# SparkFun_Color_Sensor_OPT4048.net
KiCad netlist of a schematic drawn in EAGLE
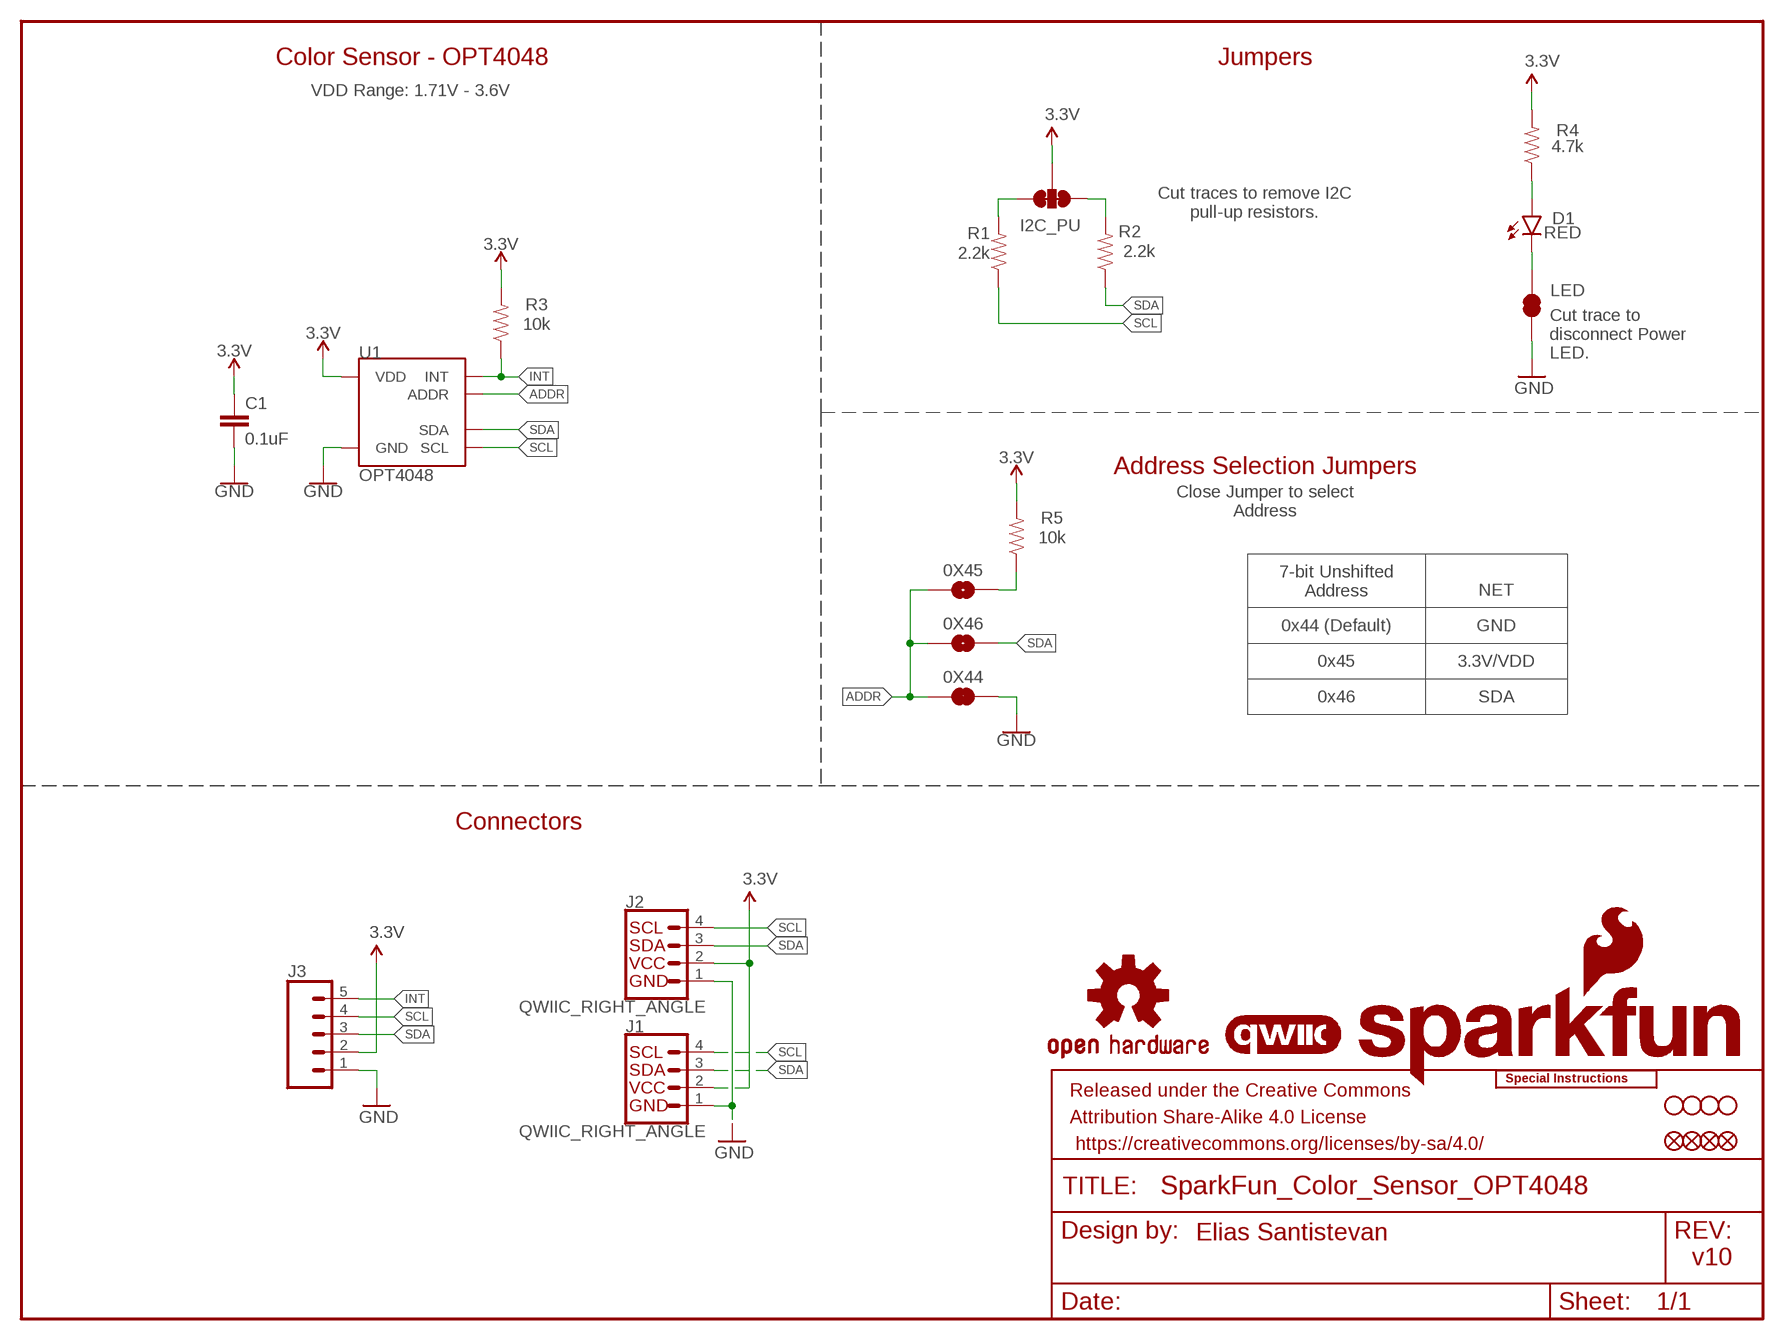
[diagram p0: schematic, sheet 1]

(export (version "E")
  (design (tool "Eeschema 10.0.6"))
  (components
    (comp (ref "0X44")
      (value "JUMPER-SMT_2_NC_TRACE_SILK")
      (footprint "eagle-import:SMT-JUMPER_2_NC_TRACE_SILK")
      (libsource (lib "eagle-import") (part "JUMPER-SMT_2_NC_TRACE_SILK"))
    )
    (comp (ref "0X45")
      (value "JUMPER-SMT_2_NO_SILK")
      (footprint "eagle-import:SMT-JUMPER_2_NO_SILK")
      (libsource (lib "eagle-import") (part "JUMPER-SMT_2_NO_SILK"))
    )
    (comp (ref "0X46")
      (value "JUMPER-SMT_2_NO_SILK")
      (footprint "eagle-import:SMT-JUMPER_2_NO_SILK")
      (libsource (lib "eagle-import") (part "JUMPER-SMT_2_NO_SILK"))
    )
    (comp (ref "C1")
      (value "0.1uF")
      (footprint "eagle-import:0402-TIGHT")
      (libsource (lib "eagle-import") (part "0.1UF-0402T-16V-10%"))
    )
    (comp (ref "D1")
      (value "RED")
      (footprint "eagle-import:LED-0603")
      (libsource (lib "eagle-import") (part "LED-RED_0603-KB"))
    )
    (comp (ref "FD1")
      (value "FIDUCIALUFIDUCIAL")
      (footprint "eagle-import:FIDUCIAL-MICRO")
      (libsource (lib "eagle-import") (part "FIDUCIALUFIDUCIAL"))
    )
    (comp (ref "FD2")
      (value "FIDUCIALUFIDUCIAL")
      (footprint "eagle-import:FIDUCIAL-MICRO")
      (libsource (lib "eagle-import") (part "FIDUCIALUFIDUCIAL"))
    )
    (comp (ref "FID1")
      (value "FIDUCIALUFIDUCIAL")
      (footprint "eagle-import:FIDUCIAL-MICRO")
      (libsource (lib "eagle-import") (part "FIDUCIALUFIDUCIAL"))
    )
    (comp (ref "FID2")
      (value "FIDUCIALUFIDUCIAL")
      (footprint "eagle-import:FIDUCIAL-MICRO")
      (libsource (lib "eagle-import") (part "FIDUCIALUFIDUCIAL"))
    )
    (comp (ref "FRAME1")
      (value "FRAME-LETTER")
      (footprint "eagle-import:CREATIVE_COMMONS")
      (fields (field (name "DESIGNER") "Elias Santistevan"))
      (libsource (lib "eagle-import") (part "FRAME-LETTER"))
    )
    (comp (ref "I2C_PU")
      (value "S_MODE")
      (footprint "eagle-import:SMT-JUMPER_3_2-NC_TRACE_SILK")
      (libsource (lib "eagle-import") (part "JUMPER-SMT_3_2-NC_TRACE_SILK"))
    )
    (comp (ref "J1")
      (value "QWIIC_RIGHT_ANGLE")
      (footprint "eagle-import:JST04_1MM_RA")
      (libsource (lib "eagle-import") (part "QWIIC_CONNECTORJS-1MM"))
    )
    (comp (ref "J2")
      (value "QWIIC_RIGHT_ANGLE")
      (footprint "eagle-import:JST04_1MM_RA")
      (libsource (lib "eagle-import") (part "QWIIC_CONNECTORJS-1MM"))
    )
    (comp (ref "J3")
      (value "CONN_05NO_SILK")
      (footprint "eagle-import:1X05_NO_SILK")
      (libsource (lib "eagle-import") (part "CONN_05NO_SILK"))
    )
    (comp (ref "LED")
      (value "JUMPER-SMT_2_NC_TRACE_SILK")
      (footprint "eagle-import:SMT-JUMPER_2_NC_TRACE_SILK")
      (libsource (lib "eagle-import") (part "JUMPER-SMT_2_NC_TRACE_SILK"))
    )
    (comp (ref "LOGO1")
      (value "QWIIC_LOGO_4MM")
      (footprint "eagle-import:QWIIC_4MM")
      (libsource (lib "eagle-import") (part "QWIIC_LOGO_4MM"))
    )
    (comp (ref "LOGO2")
      (value "OSHW-LOGOMINI")
      (footprint "eagle-import:OSHW-LOGO-MINI")
      (libsource (lib "eagle-import") (part "OSHW-LOGOMINI"))
    )
    (comp (ref "LOGO3")
      (value "SFE_LOGO_NAME_FLAME.1_INCH")
      (footprint "eagle-import:SFE_LOGO_NAME_FLAME_.1")
      (libsource (lib "eagle-import") (part "SFE_LOGO_NAME_FLAME.1_INCH"))
    )
    (comp (ref "LOGO4")
      (value "SPECIAL_INSTRUCTIONS-ORDERING")
      (footprint "eagle-import:ORDERING_INSTRUCTIONS")
      (libsource (lib "eagle-import") (part "SPECIAL_INSTRUCTIONS-ORDERING"))
    )
    (comp (ref "R1")
      (value "2.2k")
      (footprint "eagle-import:0603")
      (libsource (lib "eagle-import") (part "2.2KOHM-0603-1/10W-1%"))
    )
    (comp (ref "R2")
      (value "2.2k")
      (footprint "eagle-import:0603")
      (libsource (lib "eagle-import") (part "2.2KOHM-0603-1/10W-1%"))
    )
    (comp (ref "R3")
      (value "10k")
      (footprint "eagle-import:0603")
      (libsource (lib "eagle-import") (part "10KOHM-0603-1/10W-1%"))
    )
    (comp (ref "R4")
      (value "4.7k")
      (footprint "eagle-import:0603")
      (libsource (lib "eagle-import") (part "4.7KOHM-0603-1/10W-1%"))
    )
    (comp (ref "R5")
      (value "10k")
      (footprint "eagle-import:0603")
      (libsource (lib "eagle-import") (part "10KOHM-0603-1/10W-1%"))
    )
    (comp (ref "STANDOFF1")
      (value "STAND-OFFTIGHT")
      (footprint "eagle-import:STAND-OFF-TIGHT")
      (libsource (lib "eagle-import") (part "STAND-OFFTIGHT"))
    )
    (comp (ref "STANDOFF2")
      (value "STAND-OFFTIGHT")
      (footprint "eagle-import:STAND-OFF-TIGHT")
      (libsource (lib "eagle-import") (part "STAND-OFFTIGHT"))
    )
    (comp (ref "STANDOFF3")
      (value "STAND-OFFTIGHT")
      (footprint "eagle-import:STAND-OFF-TIGHT")
      (libsource (lib "eagle-import") (part "STAND-OFFTIGHT"))
    )
    (comp (ref "STANDOFF4")
      (value "STAND-OFFTIGHT")
      (footprint "eagle-import:STAND-OFF-TIGHT")
      (libsource (lib "eagle-import") (part "STAND-OFFTIGHT"))
    )
    (comp (ref "U1")
      (value "OPT4048")
      (footprint "eagle-import:FCSOT")
      (libsource (lib "eagle-import") (part "OPT4048"))
    )
  )
  (nets
    (net (code "1") (name "3.3V") (class "Default")
      (node (ref "C1") (pin "1") (pinfunction "1_1") (pintype "passive"))
      (node (ref "I2C_PU") (pin "2") (pinfunction "2_2") (pintype "passive"))
      (node (ref "J1") (pin "2") (pinfunction "2_2") (pintype "power_in"))
      (node (ref "J2") (pin "2") (pinfunction "2_2") (pintype "power_in"))
      (node (ref "J3") (pin "2") (pinfunction "2_2") (pintype "passive"))
      (node (ref "R3") (pin "2") (pinfunction "2_2") (pintype "passive"))
      (node (ref "R4") (pin "2") (pinfunction "2_2") (pintype "passive"))
      (node (ref "R5") (pin "2") (pinfunction "2_2") (pintype "passive"))
      (node (ref "U1") (pin "P1") (pinfunction "VDD_P1") (pintype "bidirectional"))
    )
    (net (code "2") (name "ADDR") (class "Default")
      (node (ref "0X44") (pin "1") (pinfunction "1_1") (pintype "passive"))
      (node (ref "0X45") (pin "1") (pinfunction "1_1") (pintype "passive"))
      (node (ref "0X46") (pin "1") (pinfunction "1_1") (pintype "passive"))
      (node (ref "U1") (pin "P2") (pinfunction "ADDR_P2") (pintype "bidirectional"))
    )
    (net (code "3") (name "GND") (class "Default")
      (node (ref "0X44") (pin "2") (pinfunction "2_2") (pintype "passive"))
      (node (ref "C1") (pin "2") (pinfunction "2_2") (pintype "passive"))
      (node (ref "J1") (pin "1") (pinfunction "1_1") (pintype "power_in"))
      (node (ref "J2") (pin "1") (pinfunction "1_1") (pintype "power_in"))
      (node (ref "J3") (pin "1") (pinfunction "1_1") (pintype "passive"))
      (node (ref "LED") (pin "1") (pinfunction "1_1") (pintype "passive"))
      (node (ref "U1") (pin "P4") (pinfunction "GND_P4") (pintype "bidirectional"))
    )
    (net (code "4") (name "INT") (class "Default")
      (node (ref "J3") (pin "5") (pinfunction "5_5") (pintype "passive"))
      (node (ref "R3") (pin "1") (pinfunction "1_1") (pintype "passive"))
      (node (ref "U1") (pin "P7") (pinfunction "INT_P7") (pintype "bidirectional"))
    )
    (net (code "5") (name "Net-(0X45-Pad2)") (class "Default")
      (node (ref "0X45") (pin "2") (pinfunction "2_2") (pintype "passive"))
      (node (ref "R5") (pin "1") (pinfunction "1_1") (pintype "passive"))
    )
    (net (code "6") (name "Net-(D1-PadA)") (class "Default")
      (node (ref "D1") (pin "A") (pinfunction "A_A") (pintype "passive"))
      (node (ref "R4") (pin "1") (pinfunction "1_1") (pintype "passive"))
    )
    (net (code "7") (name "Net-(D1-PadC)") (class "Default")
      (node (ref "D1") (pin "C") (pinfunction "C_C") (pintype "passive"))
      (node (ref "LED") (pin "2") (pinfunction "2_2") (pintype "passive"))
    )
    (net (code "8") (name "Net-(I2C_PU-Pad1)") (class "Default")
      (node (ref "I2C_PU") (pin "1") (pinfunction "1_1") (pintype "passive"))
      (node (ref "R1") (pin "2") (pinfunction "2_2") (pintype "passive"))
    )
    (net (code "9") (name "Net-(I2C_PU-Pad3)") (class "Default")
      (node (ref "I2C_PU") (pin "3") (pinfunction "3_3") (pintype "passive"))
      (node (ref "R2") (pin "2") (pinfunction "2_2") (pintype "passive"))
    )
    (net (code "10") (name "SCL") (class "Default")
      (node (ref "J1") (pin "4") (pinfunction "4_4") (pintype "passive"))
      (node (ref "J2") (pin "4") (pinfunction "4_4") (pintype "passive"))
      (node (ref "J3") (pin "4") (pinfunction "4_4") (pintype "passive"))
      (node (ref "R1") (pin "1") (pinfunction "1_1") (pintype "passive"))
      (node (ref "U1") (pin "P5") (pinfunction "SCL_P5") (pintype "bidirectional"))
    )
    (net (code "11") (name "SDA") (class "Default")
      (node (ref "0X46") (pin "2") (pinfunction "2_2") (pintype "passive"))
      (node (ref "J1") (pin "3") (pinfunction "3_3") (pintype "passive"))
      (node (ref "J2") (pin "3") (pinfunction "3_3") (pintype "passive"))
      (node (ref "J3") (pin "3") (pinfunction "3_3") (pintype "passive"))
      (node (ref "R2") (pin "1") (pinfunction "1_1") (pintype "passive"))
      (node (ref "U1") (pin "P8") (pinfunction "SDA_P8") (pintype "bidirectional"))
    )
  )
)
